# mainboard_rs485_v1_6.net
KiCad netlist of a schematic drawn in Altium Designer
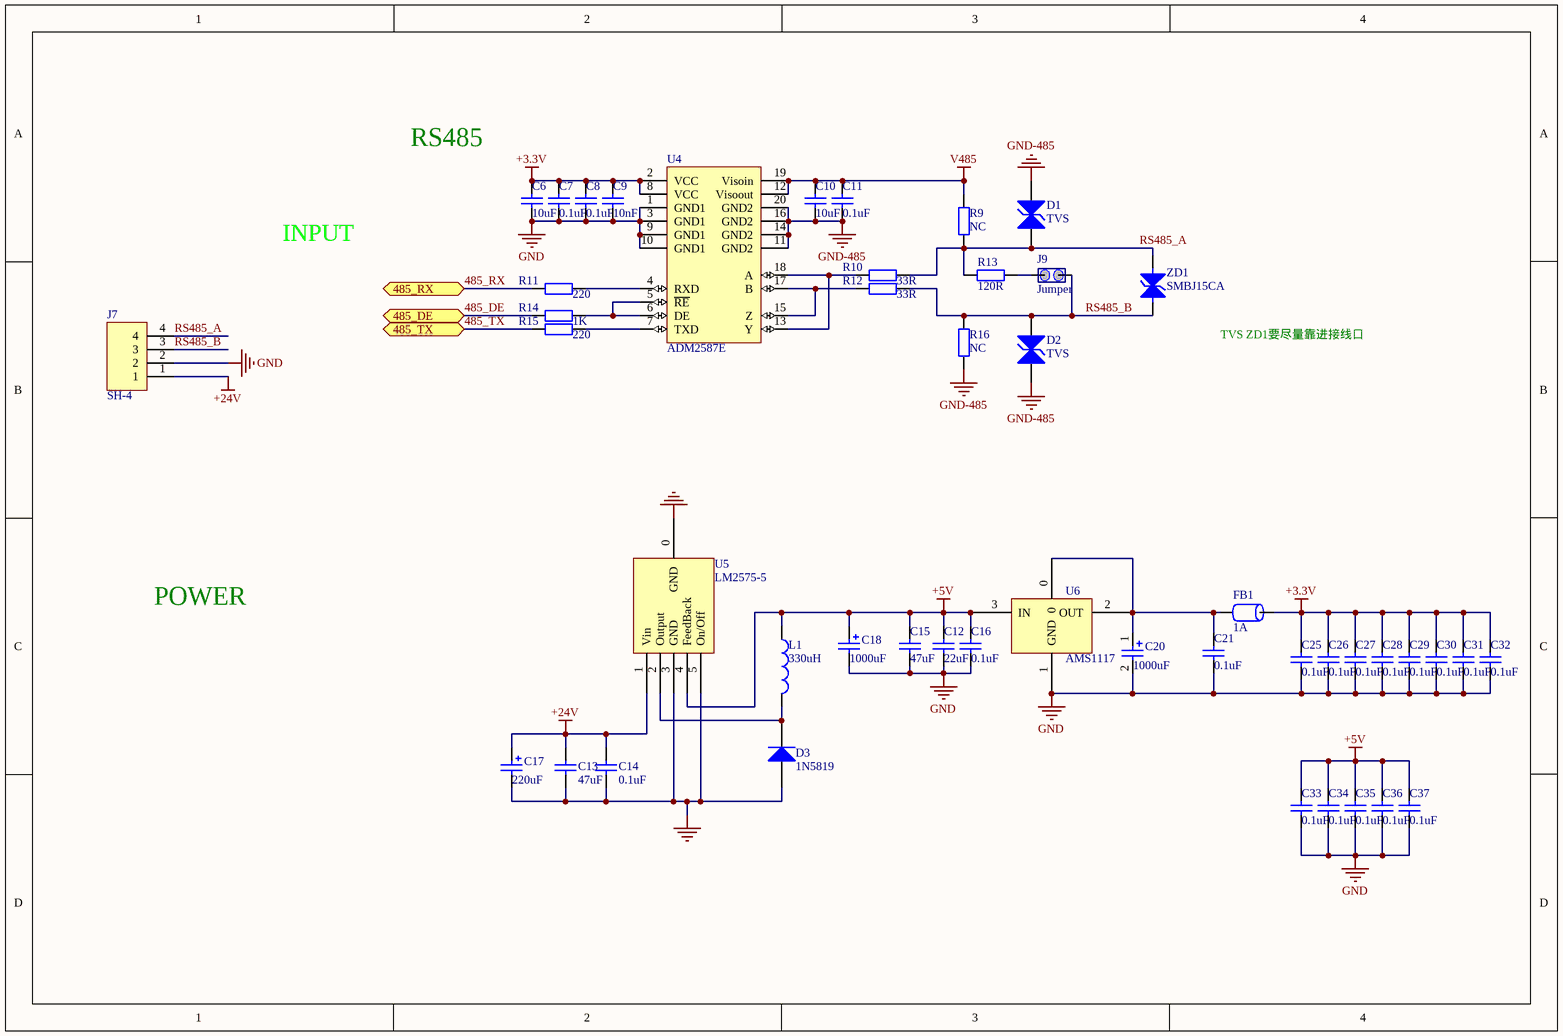
[diagram p0: mainboard_rs485.v1.6.SchDoc]

(export (version "E")
  (design (tool "Eeschema 10.0.6"))
  (components
    (comp (ref "C6")
      (value "10uF")
      (footprint "0805")
      (description "Capacitor")
      (fields (field (name "PUBLISHER") "Altium Limited"))
      (libsource (lib "TIAN's Schlib") (part "Cap"))
    )
    (comp (ref "C7")
      (value "0.1uF")
      (footprint "0805")
      (description "Capacitor")
      (fields (field (name "PUBLISHER") "Altium Limited"))
      (libsource (lib "TIAN's Schlib") (part "Cap"))
    )
    (comp (ref "C8")
      (value "0.1uF")
      (footprint "0805")
      (description "Capacitor")
      (fields (field (name "PUBLISHER") "Altium Limited"))
      (libsource (lib "TIAN's Schlib") (part "Cap"))
    )
    (comp (ref "C9")
      (value "10nF")
      (footprint "0805")
      (description "Capacitor")
      (fields (field (name "PUBLISHER") "Altium Limited"))
      (libsource (lib "TIAN's Schlib") (part "Cap"))
    )
    (comp (ref "C10")
      (value "10uF")
      (footprint "0805")
      (description "Capacitor")
      (fields (field (name "PUBLISHER") "Altium Limited"))
      (libsource (lib "TIAN's Schlib") (part "Cap"))
    )
    (comp (ref "C11")
      (value "0.1uF")
      (footprint "0805")
      (description "Capacitor")
      (fields (field (name "PUBLISHER") "Altium Limited"))
      (libsource (lib "TIAN's Schlib") (part "Cap"))
    )
    (comp (ref "C12") (value "22uF") (footprint "1206") (libsource (lib "Componet") (part "Cap0805")))
    (comp (ref "C13")
      (value "47uF")
      (footprint "1812")
      (description "Capacitor")
      (fields (field (name "PUBLISHER") "Altium Limited"))
      (libsource (lib "Miscellaneous Devices") (part "Cap"))
    )
    (comp (ref "C14")
      (value "0.1uF")
      (footprint "0805")
      (description "Capacitor")
      (fields (field (name "PUBLISHER") "Altium Limited"))
      (libsource (lib "Miscellaneous Devices") (part "Cap"))
    )
    (comp (ref "C15") (value "47uF") (footprint "1812") (libsource (lib "Componet") (part "Cap0805")))
    (comp (ref "C16") (value "0.1uF") (footprint "0805") (libsource (lib "Componet") (part "Cap0805")))
    (comp (ref "C17")
      (value "220uF")
      (footprint "CAP-5mm")
      (description "Polarized Capacitor (Radial)")
      (fields (field (name "PUBLISHER") "Altium Limited"))
      (libsource (lib "Miscellaneous Devices") (part "Cap Pol1"))
    )
    (comp (ref "C18")
      (value "1000uF")
      (footprint "CAP_SMT_10X10")
      (description "Polarized Capacitor (Radial)")
      (fields (field (name "PUBLISHER") "Altium Limited"))
      (libsource (lib "Miscellaneous Devices") (part "Cap Pol1"))
    )
    (comp (ref "C20")
      (value "1000uF")
      (footprint "CAP_SMT_10X10")
      (description "Polarized Capacitor (Radial)")
      (fields (field (name "PUBLISHER") "Altium Limited"))
      (libsource (lib "") (part "Cap Pol1_1"))
    )
    (comp (ref "C21") (value "0.1uF") (footprint "0805") (libsource (lib "Componet") (part "Cap0805")))
    (comp (ref "C25") (value "0.1uF") (footprint "0805") (libsource (lib "Componet") (part "Cap0805")))
    (comp (ref "C26") (value "0.1uF") (footprint "0805") (libsource (lib "Componet") (part "Cap0805")))
    (comp (ref "C27") (value "0.1uF") (footprint "0805") (libsource (lib "Componet") (part "Cap0805")))
    (comp (ref "C28") (value "0.1uF") (footprint "0805") (libsource (lib "Componet") (part "Cap0805")))
    (comp (ref "C29") (value "0.1uF") (footprint "0805") (libsource (lib "Componet") (part "Cap0805")))
    (comp (ref "C30") (value "0.1uF") (footprint "0805") (libsource (lib "Componet") (part "Cap0805")))
    (comp (ref "C31") (value "0.1uF") (footprint "0805") (libsource (lib "Componet") (part "Cap0805")))
    (comp (ref "C32") (value "0.1uF") (footprint "0805") (libsource (lib "Componet") (part "Cap0805")))
    (comp (ref "C33") (value "0.1uF") (footprint "0805") (libsource (lib "Componet") (part "Cap0805")))
    (comp (ref "C34") (value "0.1uF") (footprint "0805") (libsource (lib "Componet") (part "Cap0805")))
    (comp (ref "C35") (value "0.1uF") (footprint "0805") (libsource (lib "Componet") (part "Cap0805")))
    (comp (ref "C36") (value "0.1uF") (footprint "0805") (libsource (lib "Componet") (part "Cap0805")))
    (comp (ref "C37") (value "0.1uF") (footprint "0805") (libsource (lib "Componet") (part "Cap0805")))
    (comp (ref "D1")
      (value "TVS")
      (footprint "SMBJ_DO-214")
      (fields (field (name "PUBLISHER") "Altium Limited"))
      (libsource (lib "TIAN's Schlib") (part "TVS"))
    )
    (comp (ref "D2")
      (value "TVS")
      (footprint "SMBJ_DO-214")
      (fields (field (name "PUBLISHER") "Altium Limited"))
      (libsource (lib "TIAN's Schlib") (part "TVS"))
    )
    (comp (ref "D3")
      (value "1N5819")
      (footprint "Diode_TP2")
      (description "High Conductance Fast Diode")
      (fields (field (name "PUBLISHER") "Altium Limited"))
      (libsource (lib "Miscellaneous Devices") (part "Diode 1N4148"))
    )
    (comp (ref "FB1") (value "1A") (footprint "0805") (libsource (lib "Connector") (part "FERRITE")))
    (comp (ref "J7") (value "SH-4") (footprint "PWR") (libsource (lib "Connector") (part "SH-4")))
    (comp (ref "J9") (value "Jumper") (footprint "J254-2") (libsource (lib "Connector") (part "Jumper")))
    (comp (ref "L1")
      (value "330uH")
      (footprint "Inductance")
      (description "Inductor")
      (fields (field (name "PUBLISHER") "Altium Limited"))
      (libsource (lib "Miscellaneous Devices") (part "Inductor"))
    )
    (comp (ref "R9")
      (value "NC")
      (footprint "0805")
      (description "Resistor")
      (fields (field (name "PUBLISHER") "Altium Limited"))
      (libsource (lib "TIAN's Schlib") (part "Res2"))
    )
    (comp (ref "R10")
      (value "33R")
      (footprint "0805")
      (description "Resistor")
      (fields (field (name "PUBLISHER") "Altium Limited"))
      (libsource (lib "") (part "Res2_2"))
    )
    (comp (ref "R11")
      (value "220")
      (footprint "0805")
      (description "Resistor")
      (fields (field (name "PUBLISHER") "Altium Limited"))
      (libsource (lib "TIAN's Schlib") (part "Res2"))
    )
    (comp (ref "R12")
      (value "33R")
      (footprint "0805")
      (description "Resistor")
      (fields (field (name "PUBLISHER") "Altium Limited"))
      (libsource (lib "") (part "Res2_2"))
    )
    (comp (ref "R13")
      (value "120R")
      (footprint "0805")
      (description "Resistor")
      (fields (field (name "PUBLISHER") "Altium Limited"))
      (libsource (lib "") (part "Res2_1"))
    )
    (comp (ref "R14")
      (value "1K")
      (footprint "0805")
      (description "Resistor")
      (fields (field (name "PUBLISHER") "Altium Limited"))
      (libsource (lib "TIAN's Schlib") (part "Res2"))
    )
    (comp (ref "R15")
      (value "220")
      (footprint "0805")
      (description "Resistor")
      (fields (field (name "PUBLISHER") "Altium Limited"))
      (libsource (lib "TIAN's Schlib") (part "Res2"))
    )
    (comp (ref "R16")
      (value "NC")
      (footprint "0805")
      (description "Resistor")
      (fields (field (name "PUBLISHER") "Altium Limited"))
      (libsource (lib "TIAN's Schlib") (part "Res2"))
    )
    (comp (ref "U4")
      (value "ADM2587E")
      (footprint "SOIC_W_20")
      (description "isolated DC-DC RS485")
      (libsource (lib "TIAN's Schlib") (part "ADM2587E"))
    )
    (comp (ref "U5") (value "LM2575-5") (footprint "TO-263") (libsource (lib "Leon") (part "LM25XX")))
    (comp (ref "U6") (value "AMS1117") (footprint "TO-223") (libsource (lib "Chip") (part "AMS1117")))
    (comp (ref "ZD1")
      (value "SMBJ15CA")
      (footprint "DO-214AA/SMB")
      (description "瞬态抑制二极管")
      (libsource (lib "ALARM") (part "TVS"))
    )
  )
  (nets
    (net (code "1") (name "+3.3V") (class "Default")
      (node (ref "C25") (pin "2") (pinfunction "2_2") (pintype "passive"))
      (node (ref "C26") (pin "2") (pinfunction "2_2") (pintype "passive"))
      (node (ref "C27") (pin "2") (pinfunction "2_2") (pintype "passive"))
      (node (ref "C28") (pin "2") (pinfunction "2_2") (pintype "passive"))
      (node (ref "C29") (pin "2") (pinfunction "2_2") (pintype "passive"))
      (node (ref "C30") (pin "2") (pinfunction "2_2") (pintype "passive"))
      (node (ref "C31") (pin "2") (pinfunction "2_2") (pintype "passive"))
      (node (ref "C32") (pin "2") (pinfunction "2_2") (pintype "passive"))
      (node (ref "C6") (pin "2") (pinfunction "2_2") (pintype "passive"))
      (node (ref "C7") (pin "2") (pinfunction "2_2") (pintype "passive"))
      (node (ref "C8") (pin "2") (pinfunction "2_2") (pintype "passive"))
      (node (ref "C9") (pin "2") (pinfunction "2_2") (pintype "passive"))
      (node (ref "FB1") (pin "2") (pinfunction "2_2") (pintype "passive"))
      (node (ref "U4") (pin "2") (pinfunction "VCC_2") (pintype "passive"))
      (node (ref "U4") (pin "8") (pinfunction "VCC_8") (pintype "passive"))
    )
    (net (code "2") (name "+5V") (class "Default")
      (node (ref "C12") (pin "2") (pinfunction "2_2") (pintype "passive"))
      (node (ref "C15") (pin "2") (pinfunction "2_2") (pintype "passive"))
      (node (ref "C16") (pin "2") (pinfunction "2_2") (pintype "passive"))
      (node (ref "C18") (pin "1") (pinfunction "1_1") (pintype "passive"))
      (node (ref "C33") (pin "2") (pinfunction "2_2") (pintype "passive"))
      (node (ref "C34") (pin "2") (pinfunction "2_2") (pintype "passive"))
      (node (ref "C35") (pin "2") (pinfunction "2_2") (pintype "passive"))
      (node (ref "C36") (pin "2") (pinfunction "2_2") (pintype "passive"))
      (node (ref "C37") (pin "2") (pinfunction "2_2") (pintype "passive"))
      (node (ref "L1") (pin "1") (pinfunction "1_1") (pintype "passive"))
      (node (ref "U5") (pin "4") (pinfunction "FeedBack_4") (pintype "passive"))
      (node (ref "U6") (pin "3") (pinfunction "IN_3") (pintype "passive"))
    )
    (net (code "3") (name "+24V") (class "Default")
      (node (ref "C13") (pin "2") (pinfunction "2_2") (pintype "passive"))
      (node (ref "C14") (pin "2") (pinfunction "2_2") (pintype "passive"))
      (node (ref "C17") (pin "1") (pinfunction "1_1") (pintype "passive"))
      (node (ref "J7") (pin "1") (pinfunction "1_1") (pintype "passive"))
      (node (ref "U5") (pin "1") (pinfunction "Vin_1") (pintype "passive"))
    )
    (net (code "4") (name "/485_DE") (class "Default")
      (node (ref "R14") (pin "1") (pinfunction "1_1") (pintype "passive"))
    )
    (net (code "5") (name "/485_RX") (class "Default")
      (node (ref "R11") (pin "1") (pinfunction "1_1") (pintype "passive"))
    )
    (net (code "6") (name "/485_TX") (class "Default")
      (node (ref "R15") (pin "1") (pinfunction "1_1") (pintype "passive"))
    )
    (net (code "7") (name "/RS485_A") (class "Default")
      (node (ref "D1") (pin "2") (pinfunction "K_2") (pintype "passive"))
      (node (ref "J7") (pin "4") (pinfunction "4_4") (pintype "passive"))
      (node (ref "R10") (pin "2") (pinfunction "2_2") (pintype "passive"))
      (node (ref "R13") (pin "2") (pinfunction "2_2") (pintype "passive"))
      (node (ref "R9") (pin "1") (pinfunction "1_1") (pintype "passive"))
      (node (ref "ZD1") (pin "1") (pinfunction "1_1") (pintype "passive"))
    )
    (net (code "8") (name "/RS485_B") (class "Default")
      (node (ref "D2") (pin "2") (pinfunction "K_2") (pintype "passive"))
      (node (ref "J7") (pin "3") (pinfunction "3_3") (pintype "passive"))
      (node (ref "J9") (pin "1") (pinfunction "1_1") (pintype "passive"))
      (node (ref "R12") (pin "2") (pinfunction "2_2") (pintype "passive"))
      (node (ref "R16") (pin "2") (pinfunction "2_2") (pintype "passive"))
      (node (ref "ZD1") (pin "2") (pinfunction "2_2") (pintype "passive"))
    )
    (net (code "9") (name "GND") (class "Default")
      (node (ref "C12") (pin "1") (pinfunction "1_1") (pintype "passive"))
      (node (ref "C13") (pin "1") (pinfunction "1_1") (pintype "passive"))
      (node (ref "C14") (pin "1") (pinfunction "1_1") (pintype "passive"))
      (node (ref "C15") (pin "1") (pinfunction "1_1") (pintype "passive"))
      (node (ref "C16") (pin "1") (pinfunction "1_1") (pintype "passive"))
      (node (ref "C17") (pin "2") (pinfunction "2_2") (pintype "passive"))
      (node (ref "C18") (pin "2") (pinfunction "2_2") (pintype "passive"))
      (node (ref "C20") (pin "2") (pinfunction "2_2") (pintype "passive"))
      (node (ref "C21") (pin "1") (pinfunction "1_1") (pintype "passive"))
      (node (ref "C25") (pin "1") (pinfunction "1_1") (pintype "passive"))
      (node (ref "C26") (pin "1") (pinfunction "1_1") (pintype "passive"))
      (node (ref "C27") (pin "1") (pinfunction "1_1") (pintype "passive"))
      (node (ref "C28") (pin "1") (pinfunction "1_1") (pintype "passive"))
      (node (ref "C29") (pin "1") (pinfunction "1_1") (pintype "passive"))
      (node (ref "C30") (pin "1") (pinfunction "1_1") (pintype "passive"))
      (node (ref "C31") (pin "1") (pinfunction "1_1") (pintype "passive"))
      (node (ref "C32") (pin "1") (pinfunction "1_1") (pintype "passive"))
      (node (ref "C33") (pin "1") (pinfunction "1_1") (pintype "passive"))
      (node (ref "C34") (pin "1") (pinfunction "1_1") (pintype "passive"))
      (node (ref "C35") (pin "1") (pinfunction "1_1") (pintype "passive"))
      (node (ref "C36") (pin "1") (pinfunction "1_1") (pintype "passive"))
      (node (ref "C37") (pin "1") (pinfunction "1_1") (pintype "passive"))
      (node (ref "C6") (pin "1") (pinfunction "1_1") (pintype "passive"))
      (node (ref "C7") (pin "1") (pinfunction "1_1") (pintype "passive"))
      (node (ref "C8") (pin "1") (pinfunction "1_1") (pintype "passive"))
      (node (ref "C9") (pin "1") (pinfunction "1_1") (pintype "passive"))
      (node (ref "D3") (pin "1") (pinfunction "A_1") (pintype "passive"))
      (node (ref "J7") (pin "2") (pinfunction "2_2") (pintype "passive"))
      (node (ref "U4") (pin "1") (pinfunction "GND1_1") (pintype "passive"))
      (node (ref "U4") (pin "10") (pinfunction "GND1_10") (pintype "passive"))
      (node (ref "U4") (pin "3") (pinfunction "GND1_3") (pintype "passive"))
      (node (ref "U4") (pin "9") (pinfunction "GND1_9") (pintype "passive"))
      (node (ref "U5") (pin "0") (pinfunction "GND_0") (pintype "passive"))
      (node (ref "U5") (pin "3") (pinfunction "GND_3") (pintype "passive"))
      (node (ref "U5") (pin "5") (pinfunction "On/Off_5") (pintype "passive"))
      (node (ref "U6") (pin "1") (pinfunction "GND_1") (pintype "passive"))
    )
    (net (code "10") (name "GND-485") (class "Default")
      (node (ref "C10") (pin "1") (pinfunction "1_1") (pintype "passive"))
      (node (ref "C11") (pin "1") (pinfunction "1_1") (pintype "passive"))
      (node (ref "D1") (pin "1") (pinfunction "A_1") (pintype "passive"))
      (node (ref "D2") (pin "1") (pinfunction "A_1") (pintype "passive"))
      (node (ref "R16") (pin "1") (pinfunction "1_1") (pintype "passive"))
      (node (ref "U4") (pin "11") (pinfunction "GND2_11") (pintype "passive"))
      (node (ref "U4") (pin "14") (pinfunction "GND2_14") (pintype "passive"))
      (node (ref "U4") (pin "16") (pinfunction "GND2_16") (pintype "passive"))
      (node (ref "U4") (pin "20") (pinfunction "GND2_20") (pintype "passive"))
    )
    (net (code "11") (name "Net-(D3-K)") (class "Default")
      (node (ref "D3") (pin "2") (pinfunction "K_2") (pintype "passive"))
      (node (ref "L1") (pin "2") (pinfunction "2_2") (pintype "passive"))
      (node (ref "U5") (pin "2") (pinfunction "Output_2") (pintype "passive"))
    )
    (net (code "12") (name "Net-(J9-Pad2)") (class "Default")
      (node (ref "J9") (pin "2") (pinfunction "2_2") (pintype "passive"))
      (node (ref "R13") (pin "1") (pinfunction "1_1") (pintype "passive"))
    )
    (net (code "13") (name "Net-(U4-A)") (class "Default")
      (node (ref "R10") (pin "1") (pinfunction "1_1") (pintype "passive"))
      (node (ref "U4") (pin "13") (pinfunction "Y_13") (pintype "bidirectional"))
      (node (ref "U4") (pin "18") (pinfunction "A_18") (pintype "bidirectional"))
    )
    (net (code "14") (name "Net-(U4-B)") (class "Default")
      (node (ref "R12") (pin "1") (pinfunction "1_1") (pintype "passive"))
      (node (ref "U4") (pin "15") (pinfunction "Z_15") (pintype "bidirectional"))
      (node (ref "U4") (pin "17") (pinfunction "B_17") (pintype "bidirectional"))
    )
    (net (code "15") (name "Net-(U4-DE)") (class "Default")
      (node (ref "R14") (pin "2") (pinfunction "2_2") (pintype "passive"))
      (node (ref "U4") (pin "5") (pinfunction "~{RE}_5") (pintype "bidirectional"))
      (node (ref "U4") (pin "6") (pinfunction "DE_6") (pintype "bidirectional"))
    )
    (net (code "16") (name "Net-(U4-RXD)") (class "Default")
      (node (ref "R11") (pin "2") (pinfunction "2_2") (pintype "passive"))
      (node (ref "U4") (pin "4") (pinfunction "RXD_4") (pintype "bidirectional"))
    )
    (net (code "17") (name "Net-(U4-TXD)") (class "Default")
      (node (ref "R15") (pin "2") (pinfunction "2_2") (pintype "passive"))
      (node (ref "U4") (pin "7") (pinfunction "TXD_7") (pintype "bidirectional"))
    )
    (net (code "18") (name "Net-(U6-OUT)") (class "Default")
      (node (ref "C20") (pin "1") (pinfunction "1_1") (pintype "passive"))
      (node (ref "C21") (pin "2") (pinfunction "2_2") (pintype "passive"))
      (node (ref "FB1") (pin "1") (pinfunction "1_1") (pintype "passive"))
      (node (ref "U6") (pin "0") (pinfunction "0_0") (pintype "passive"))
      (node (ref "U6") (pin "2") (pinfunction "OUT_2") (pintype "passive"))
    )
    (net (code "19") (name "V485") (class "Default")
      (node (ref "C10") (pin "2") (pinfunction "2_2") (pintype "passive"))
      (node (ref "C11") (pin "2") (pinfunction "2_2") (pintype "passive"))
      (node (ref "R9") (pin "2") (pinfunction "2_2") (pintype "passive"))
      (node (ref "U4") (pin "12") (pinfunction "Visoout_12") (pintype "passive"))
      (node (ref "U4") (pin "19") (pinfunction "Visoin_19") (pintype "passive"))
    )
  )
)
